# ETH10M100_MAGNET.net
KiCad netlist of a schematic drawn in Altium Designer
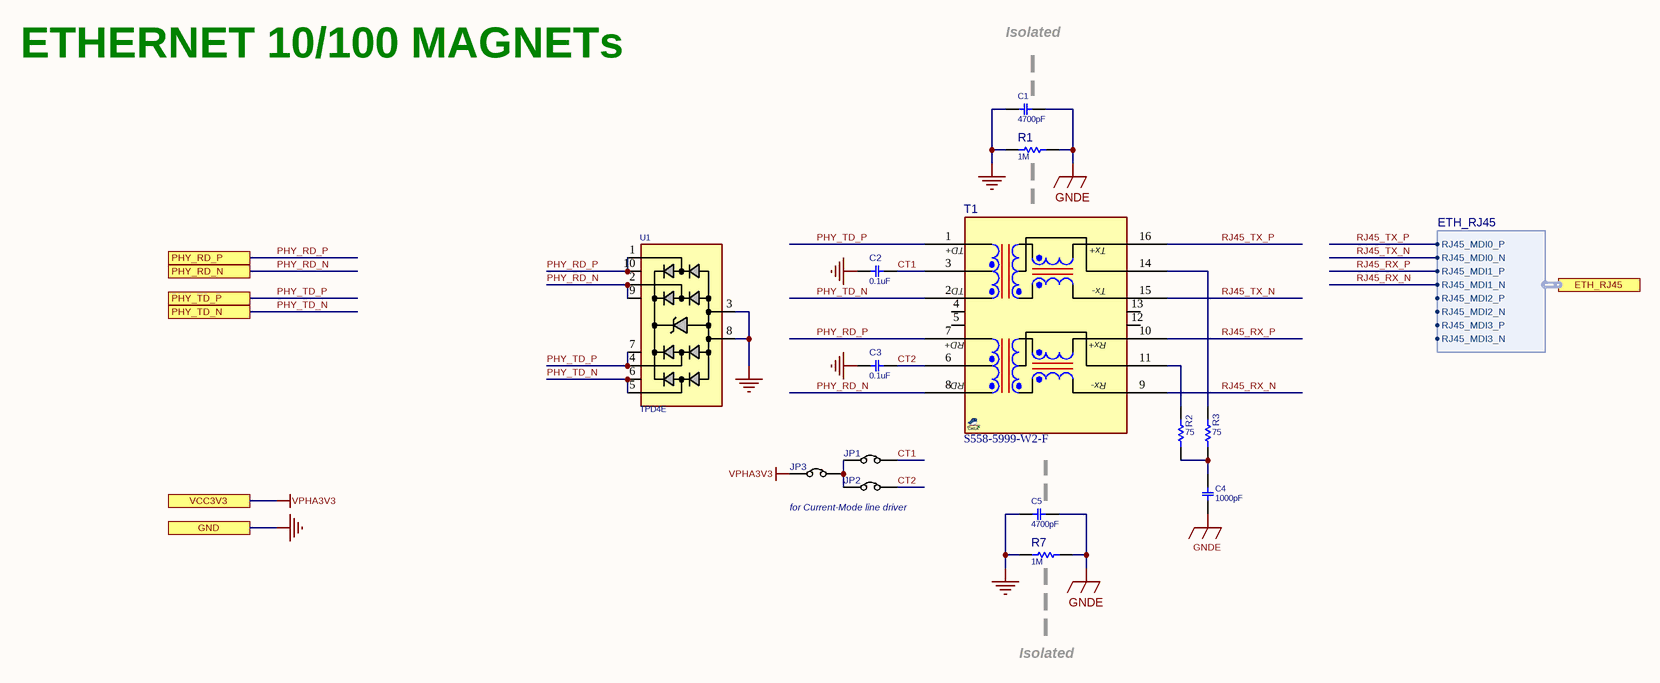
[diagram p0: ETH10M100_MAGNET.SchDoc]

(export (version "E")
  (design (tool "Eeschema 10.0.6"))
  (components
    (comp (ref "C1")
      (value "4700pF")
      (footprint "C1206")
      (description "CAP, MLCC")
      (fields (field (name "MANF_P#") "NV1206B472K202CEGN") (field (name "MANF") "KEMET"))
      (libsource (lib "mlcc_smd_passive") (part "CAP_SMD_MLCC_68n1kv"))
    )
    (comp (ref "C2")
      (value "0.1uF")
      (footprint "C0402")
      (description "CAP, MLCC")
      (libsource (lib "mlcc_smd_passive") (part "CAP_SMD_MLCC_22n50V"))
    )
    (comp (ref "C3")
      (value "0.1uF")
      (footprint "C0402")
      (description "CAP, MLCC")
      (libsource (lib "mlcc_smd_passive") (part "CAP_SMD_MLCC_22n50V"))
    )
    (comp (ref "C4")
      (value "1000pF")
      (footprint "C1206")
      (description "CAP, MLCC")
      (fields (field (name "MANF_P#") "1206B102K202NT"))
      (libsource (lib "mlcc_smd_passive") (part "CAP_SMD_MLCC_22n50V"))
    )
    (comp (ref "C5")
      (value "4700pF")
      (footprint "C1206")
      (description "CAP, MLCC")
      (fields (field (name "MANF_P#") "NV1206B472K202CEGN") (field (name "MANF") "KEMET"))
      (libsource (lib "mlcc_smd_passive") (part "CAP_SMD_MLCC_68n1kv"))
    )
    (comp (ref "JP1")
      (value "JMPSOLDER")
      (footprint "JP_30X50")
      (description "JUMPER, HEADER 2PIN")
      (fields (field (name "MANF") "MANF") (field (name "MANF_P#") "MANF_P#"))
      (libsource (lib "test-tp_jumper") (part "JUMPER_SOLDER"))
    )
    (comp (ref "JP2")
      (value "JMPSOLDER")
      (footprint "JP_30X50")
      (description "JUMPER, HEADER 2PIN")
      (fields (field (name "MANF") "MANF") (field (name "MANF_P#") "MANF_P#"))
      (libsource (lib "test-tp_jumper") (part "JUMPER_SOLDER"))
    )
    (comp (ref "JP3")
      (value "JMPSOLDER")
      (footprint "JP_30X50")
      (description "JUMPER, HEADER 2PIN")
      (fields (field (name "MANF") "MANF") (field (name "MANF_P#") "MANF_P#"))
      (libsource (lib "test-tp_jumper") (part "JUMPER_SOLDER"))
    )
    (comp (ref "R1")
      (value "1M")
      (footprint "R2512")
      (description "RESISTOR, SMD")
      (fields (field (name "MANF_P#") "FRC2512J105 TS"))
      (libsource (lib "chila_passive") (part "RES_SMD"))
    )
    (comp (ref "R2")
      (value "75")
      (footprint "R0603O")
      (description "RESISTOR, SMD, THICK FILM, YAGEO")
      (fields (field (name "MANF_P#") "RC0402FR-071KL") (field (name "MANF") "Yageo"))
      (libsource (lib "res_smd_Yageo0402_thickfilm") (part "RES_SMD_1K_0402YK"))
    )
    (comp (ref "R3")
      (value "75")
      (footprint "R0603O")
      (description "RESISTOR, SMD, THICK FILM, YAGEO")
      (fields (field (name "MANF_P#") "RC0402FR-071KL") (field (name "MANF") "Yageo"))
      (libsource (lib "res_smd_Yageo0402_thickfilm") (part "RES_SMD_1K_0402YK"))
    )
    (comp (ref "R7")
      (value "1M")
      (footprint "R2512")
      (description "RESISTOR, SMD")
      (fields (field (name "MANF_P#") "FRC2512J105 TS"))
      (libsource (lib "chila_passive") (part "RES_SMD"))
    )
    (comp (ref "T1")
      (value "S558-5999-W2-F")
      (footprint "SO_16_7W6H")
      (description "Transformer, LAN, 10/100 Base-T, 1CT:1CT, 350uH")
      (fields (field (name "MANF") "Bel"))
      (libsource (lib "transformer_ethernet") (part "S558-5999-W2-F_SO16"))
    )
    (comp (ref "U1")
      (value "TPD4E")
      (footprint "SON50_10_2510")
      (description "TVS, ESD PROTECT, 4CH,")
      (fields (field (name "MANF_P#") "TPD4E05U06DQA") (field (name "MANF") "Texas Instruments"))
      (libsource (lib "protect_tvs_esd_fuse") (part "TVS_X4_TPD4E05U06"))
    )
  )
  (nets
    (net (code "2") (name "/CT1") (class "Default")
      (node (ref "C2") (pin "2") (pinfunction "2_2") (pintype "passive"))
      (node (ref "JP1") (pin "2") (pinfunction "2_2") (pintype "passive"))
      (node (ref "T1") (pin "3") (pinfunction "TDCT_3") (pintype "passive"))
    )
    (net (code "3") (name "/CT2") (class "Default")
      (node (ref "C3") (pin "2") (pinfunction "2_2") (pintype "passive"))
      (node (ref "JP2") (pin "2") (pinfunction "2_2") (pintype "passive"))
      (node (ref "T1") (pin "6") (pinfunction "RDCT_6") (pintype "passive"))
    )
    (net (code "4") (name "/PHY_RD_N") (class "Default")
      (node (ref "T1") (pin "8") (pinfunction "RD-_8") (pintype "passive"))
      (node (ref "U1") (pin "2") (pinfunction "2_2") (pintype "passive"))
      (node (ref "U1") (pin "9") (pinfunction "9_9") (pintype "passive"))
    )
    (net (code "5") (name "/PHY_RD_P") (class "Default")
      (node (ref "T1") (pin "7") (pinfunction "RD+_7") (pintype "passive"))
      (node (ref "U1") (pin "1") (pinfunction "1_1") (pintype "passive"))
      (node (ref "U1") (pin "10") (pinfunction "10_10") (pintype "passive"))
    )
    (net (code "6") (name "/PHY_TD_N") (class "Default")
      (node (ref "T1") (pin "2") (pinfunction "TD-_2") (pintype "passive"))
      (node (ref "U1") (pin "5") (pinfunction "5_5") (pintype "passive"))
      (node (ref "U1") (pin "6") (pinfunction "6_6") (pintype "passive"))
    )
    (net (code "7") (name "/PHY_TD_P") (class "Default")
      (node (ref "T1") (pin "1") (pinfunction "TD+_1") (pintype "passive"))
      (node (ref "U1") (pin "4") (pinfunction "4_4") (pintype "passive"))
      (node (ref "U1") (pin "7") (pinfunction "7_7") (pintype "passive"))
    )
    (net (code "8") (name "/RJ45_RX_N") (class "Default")
      (node (ref "T1") (pin "9") (pinfunction "RX-_9") (pintype "passive"))
    )
    (net (code "9") (name "/RJ45_RX_P") (class "Default")
      (node (ref "T1") (pin "10") (pinfunction "RX+_10") (pintype "passive"))
    )
    (net (code "10") (name "/RJ45_TX_N") (class "Default")
      (node (ref "T1") (pin "15") (pinfunction "TX-_15") (pintype "passive"))
    )
    (net (code "11") (name "/RJ45_TX_P") (class "Default")
      (node (ref "T1") (pin "16") (pinfunction "TX+_16") (pintype "passive"))
    )
    (net (code "13") (name "GND") (class "Default")
      (node (ref "C1") (pin "1") (pinfunction "1_1") (pintype "passive"))
      (node (ref "C2") (pin "1") (pinfunction "1_1") (pintype "passive"))
      (node (ref "C3") (pin "1") (pinfunction "1_1") (pintype "passive"))
      (node (ref "C5") (pin "1") (pinfunction "1_1") (pintype "passive"))
      (node (ref "R1") (pin "2") (pinfunction "2_2") (pintype "passive"))
      (node (ref "R7") (pin "2") (pinfunction "2_2") (pintype "passive"))
      (node (ref "U1") (pin "3") (pinfunction "3_3") (pintype "passive"))
      (node (ref "U1") (pin "8") (pinfunction "8_8") (pintype "passive"))
    )
    (net (code "14") (name "GNDE") (class "Default")
      (node (ref "C1") (pin "2") (pinfunction "2_2") (pintype "passive"))
      (node (ref "C4") (pin "2") (pinfunction "2_2") (pintype "passive"))
      (node (ref "C5") (pin "2") (pinfunction "2_2") (pintype "passive"))
      (node (ref "R1") (pin "1") (pinfunction "1_1") (pintype "passive"))
      (node (ref "R7") (pin "1") (pinfunction "1_1") (pintype "passive"))
    )
    (net (code "15") (name "Net-(C4-Pad1)") (class "Default")
      (node (ref "C4") (pin "1") (pinfunction "1_1") (pintype "passive"))
      (node (ref "R2") (pin "2") (pinfunction "2_2") (pintype "passive"))
      (node (ref "R3") (pin "2") (pinfunction "2_2") (pintype "passive"))
    )
    (net (code "16") (name "Net-(JP1-Pad1)") (class "Default")
      (node (ref "JP1") (pin "1") (pinfunction "1_1") (pintype "passive"))
      (node (ref "JP2") (pin "1") (pinfunction "1_1") (pintype "passive"))
      (node (ref "JP3") (pin "2") (pinfunction "2_2") (pintype "passive"))
    )
    (net (code "17") (name "Net-(T1-RXCT)") (class "Default")
      (node (ref "R2") (pin "1") (pinfunction "1_1") (pintype "passive"))
      (node (ref "T1") (pin "11") (pinfunction "RXCT_11") (pintype "passive"))
    )
    (net (code "18") (name "Net-(T1-TXCT)") (class "Default")
      (node (ref "R3") (pin "1") (pinfunction "1_1") (pintype "passive"))
      (node (ref "T1") (pin "14") (pinfunction "TXCT_14") (pintype "passive"))
    )
    (net (code "19") (name "VPHA3V3") (class "Default")
      (node (ref "JP3") (pin "1") (pinfunction "1_1") (pintype "passive"))
    )
    (net (code "20") (name "unconnected-(T1-NC_1-Pad4)") (class "Default")
      (node (ref "T1") (pin "4") (pinfunction "NC_1_4") (pintype "passive"))
    )
    (net (code "21") (name "unconnected-(T1-NC_2-Pad5)") (class "Default")
      (node (ref "T1") (pin "5") (pinfunction "NC_2_5") (pintype "passive"))
    )
    (net (code "22") (name "unconnected-(T1-NC_3-Pad12)") (class "Default")
      (node (ref "T1") (pin "12") (pinfunction "NC_3_12") (pintype "passive"))
    )
    (net (code "23") (name "unconnected-(T1-NC_4-Pad13)") (class "Default")
      (node (ref "T1") (pin "13") (pinfunction "NC_4_13") (pintype "passive"))
    )
  )
)
